# tiips_tag.net
KiCad netlist of a schematic drawn in EAGLE
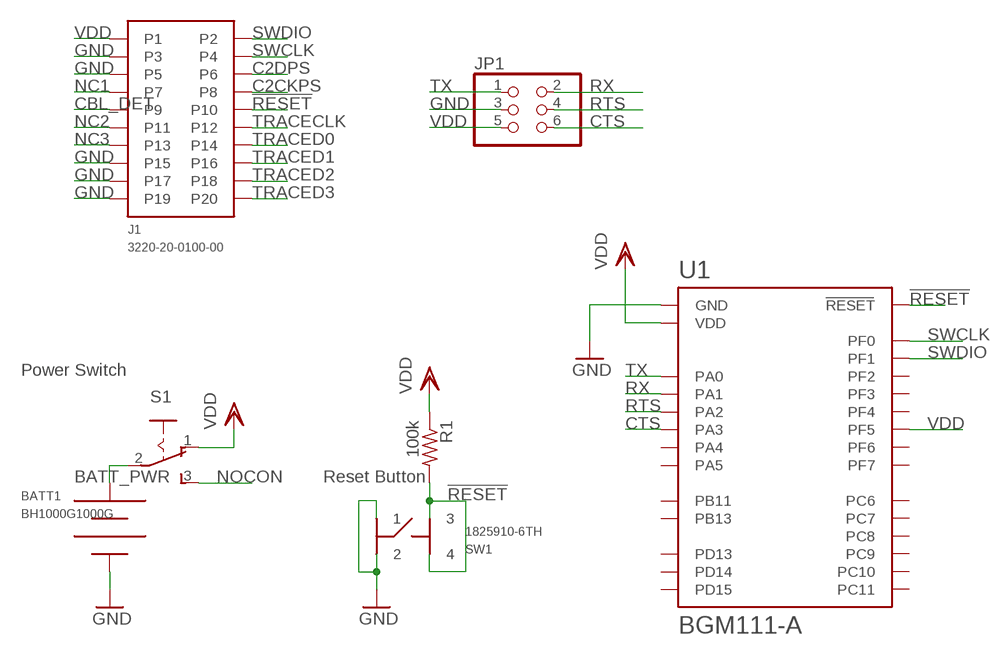
[diagram p0: schematic, sheet 1]

(export (version "E")
  (design (tool "Eeschema 10.0.6"))
  (components
    (comp (ref "BATT1")
      (value "BH1000G1000G")
      (footprint "eagle-import:BH")
      (libsource (lib "eagle-import") (part "BH1000G1000G"))
    )
    (comp (ref "J1")
      (value "3220-20-0100-00")
      (footprint "eagle-import:3220-20-0100-00")
      (libsource (lib "eagle-import") (part "3220-20-0100-00"))
    )
    (comp (ref "JP1")
      (value "PINHD-2X3")
      (footprint "eagle-import:2X03")
      (libsource (lib "eagle-import") (part "PINHD-2X3"))
    )
    (comp (ref "R1")
      (value "100k")
      (footprint "eagle-import:0309_10")
      (libsource (lib "eagle-import") (part "R-US_0309/10"))
    )
    (comp (ref "S1")
      (value "M251")
      (footprint "eagle-import:M251")
      (libsource (lib "eagle-import") (part "M251"))
    )
    (comp (ref "SW1")
      (value "1825910-6TH")
      (footprint "eagle-import:1825910-6")
      (libsource (lib "eagle-import") (part "1825910-6TH"))
    )
    (comp (ref "U1")
      (value "BGM111-A")
      (footprint "eagle-import:BGM111-A")
      (libsource (lib "eagle-import") (part "BGM111-A"))
    )
  )
  (nets
    (net (code "1") (name "/BATT_PWR") (class "Default")
      (node (ref "BATT1") (pin "2") (pinfunction "3V_2") (pintype "power_in"))
      (node (ref "S1") (pin "2") (pinfunction "P_2") (pintype "passive"))
    )
    (net (code "2") (name "/C2CKPS") (class "Default")
      (node (ref "J1") (pin "P8") (pinfunction "P8_P8") (pintype "bidirectional"))
    )
    (net (code "3") (name "/C2DPS") (class "Default")
      (node (ref "J1") (pin "P6") (pinfunction "P6_P6") (pintype "bidirectional"))
    )
    (net (code "4") (name "/CBL_DET") (class "Default")
      (node (ref "J1") (pin "P9") (pinfunction "P9_P9") (pintype "bidirectional"))
    )
    (net (code "5") (name "/CTS") (class "Default")
      (node (ref "JP1") (pin "6") (pinfunction "6_6") (pintype "passive"))
      (node (ref "U1") (pin "PA3") (pinfunction "PA3_PA3") (pintype "bidirectional"))
    )
    (net (code "6") (name "/NC1") (class "Default")
      (node (ref "J1") (pin "P7") (pinfunction "P7_P7") (pintype "bidirectional"))
    )
    (net (code "7") (name "/NC2") (class "Default")
      (node (ref "J1") (pin "P11") (pinfunction "P11_P11") (pintype "bidirectional"))
    )
    (net (code "8") (name "/NC3") (class "Default")
      (node (ref "J1") (pin "P13") (pinfunction "P13_P13") (pintype "bidirectional"))
    )
    (net (code "9") (name "/NOCON") (class "Default")
      (node (ref "S1") (pin "3") (pinfunction "S_3") (pintype "passive"))
    )
    (net (code "10") (name "/RTS") (class "Default")
      (node (ref "JP1") (pin "4") (pinfunction "4_4") (pintype "passive"))
      (node (ref "U1") (pin "PA2") (pinfunction "PA2_PA2") (pintype "bidirectional"))
    )
    (net (code "11") (name "/RX") (class "Default")
      (node (ref "JP1") (pin "2") (pinfunction "2_2") (pintype "passive"))
      (node (ref "U1") (pin "PA1") (pinfunction "PA1_PA1") (pintype "bidirectional"))
    )
    (net (code "12") (name "/SWCLK") (class "Default")
      (node (ref "J1") (pin "P4") (pinfunction "P4_P4") (pintype "bidirectional"))
      (node (ref "U1") (pin "PF0") (pinfunction "PF0_PF0") (pintype "bidirectional"))
    )
    (net (code "13") (name "/SWDIO") (class "Default")
      (node (ref "J1") (pin "P2") (pinfunction "P2_P2") (pintype "bidirectional"))
      (node (ref "U1") (pin "PF1") (pinfunction "PF1_PF1") (pintype "bidirectional"))
    )
    (net (code "14") (name "/TRACECLK") (class "Default")
      (node (ref "J1") (pin "P12") (pinfunction "P12_P12") (pintype "bidirectional"))
    )
    (net (code "15") (name "/TRACED0") (class "Default")
      (node (ref "J1") (pin "P14") (pinfunction "P14_P14") (pintype "bidirectional"))
    )
    (net (code "16") (name "/TRACED1") (class "Default")
      (node (ref "J1") (pin "P16") (pinfunction "P16_P16") (pintype "bidirectional"))
    )
    (net (code "17") (name "/TRACED2") (class "Default")
      (node (ref "J1") (pin "P18") (pinfunction "P18_P18") (pintype "bidirectional"))
    )
    (net (code "18") (name "/TRACED3") (class "Default")
      (node (ref "J1") (pin "P20") (pinfunction "P20_P20") (pintype "bidirectional"))
    )
    (net (code "19") (name "/TX") (class "Default")
      (node (ref "JP1") (pin "1") (pinfunction "1_1") (pintype "passive"))
      (node (ref "U1") (pin "PA0") (pinfunction "PA0_PA0") (pintype "bidirectional"))
    )
    (net (code "20") (name "/~{RESET}") (class "Default")
      (node (ref "J1") (pin "P10") (pinfunction "P10_P10") (pintype "bidirectional"))
      (node (ref "R1") (pin "2") (pinfunction "2_2") (pintype "passive"))
      (node (ref "SW1") (pin "3") (pinfunction "3_3") (pintype "power_in"))
      (node (ref "SW1") (pin "4") (pinfunction "4_4") (pintype "power_in"))
      (node (ref "U1") (pin "RESET") (pinfunction "RESET_RESET") (pintype "input"))
    )
    (net (code "21") (name "GND") (class "Default")
      (node (ref "BATT1") (pin "1") (pinfunction "GND_1") (pintype "power_in"))
      (node (ref "J1") (pin "P15") (pinfunction "P15_P15") (pintype "bidirectional"))
      (node (ref "J1") (pin "P17") (pinfunction "P17_P17") (pintype "bidirectional"))
      (node (ref "J1") (pin "P19") (pinfunction "P19_P19") (pintype "bidirectional"))
      (node (ref "J1") (pin "P3") (pinfunction "P3_P3") (pintype "bidirectional"))
      (node (ref "J1") (pin "P5") (pinfunction "P5_P5") (pintype "bidirectional"))
      (node (ref "JP1") (pin "3") (pinfunction "3_3") (pintype "passive"))
      (node (ref "SW1") (pin "1") (pinfunction "1_1") (pintype "power_in"))
      (node (ref "SW1") (pin "2") (pinfunction "2_2") (pintype "power_in"))
      (node (ref "U1") (pin "GND") (pinfunction "GND_GND") (pintype "power_in"))
      (node (ref "U1") (pin "GND@2") (pinfunction "GND_GND@2") (pintype "power_in"))
      (node (ref "U1") (pin "GND@3") (pinfunction "GND_GND@3") (pintype "power_in"))
      (node (ref "U1") (pin "GND@4") (pinfunction "GND_GND@4") (pintype "power_in"))
    )
    (net (code "22") (name "VDD") (class "Default")
      (node (ref "J1") (pin "P1") (pinfunction "P1_P1") (pintype "bidirectional"))
      (node (ref "JP1") (pin "5") (pinfunction "5_5") (pintype "passive"))
      (node (ref "R1") (pin "1") (pinfunction "1_1") (pintype "passive"))
      (node (ref "S1") (pin "1") (pinfunction "O_1") (pintype "passive"))
      (node (ref "U1") (pin "PF5") (pinfunction "PF5_PF5") (pintype "bidirectional"))
      (node (ref "U1") (pin "VDD") (pinfunction "VDD_VDD") (pintype "power_in"))
    )
    (net (code "23") (name "unconnected-(U1-PadPA4)") (class "Default")
      (node (ref "U1") (pin "PA4") (pinfunction "PA4_PA4") (pintype "bidirectional"))
    )
    (net (code "24") (name "unconnected-(U1-PadPA5)") (class "Default")
      (node (ref "U1") (pin "PA5") (pinfunction "PA5_PA5") (pintype "bidirectional"))
    )
    (net (code "25") (name "unconnected-(U1-PadPB11)") (class "Default")
      (node (ref "U1") (pin "PB11") (pinfunction "PB11_PB11") (pintype "bidirectional"))
    )
    (net (code "26") (name "unconnected-(U1-PadPB13)") (class "Default")
      (node (ref "U1") (pin "PB13") (pinfunction "PB13_PB13") (pintype "bidirectional"))
    )
    (net (code "27") (name "unconnected-(U1-PadPC6)") (class "Default")
      (node (ref "U1") (pin "PC6") (pinfunction "PC6_PC6") (pintype "bidirectional"))
    )
    (net (code "28") (name "unconnected-(U1-PadPC7)") (class "Default")
      (node (ref "U1") (pin "PC7") (pinfunction "PC7_PC7") (pintype "bidirectional"))
    )
    (net (code "29") (name "unconnected-(U1-PadPC8)") (class "Default")
      (node (ref "U1") (pin "PC8") (pinfunction "PC8_PC8") (pintype "bidirectional"))
    )
    (net (code "30") (name "unconnected-(U1-PadPC9)") (class "Default")
      (node (ref "U1") (pin "PC9") (pinfunction "PC9_PC9") (pintype "bidirectional"))
    )
    (net (code "31") (name "unconnected-(U1-PadPC10)") (class "Default")
      (node (ref "U1") (pin "PC10") (pinfunction "PC10_PC10") (pintype "bidirectional"))
    )
    (net (code "32") (name "unconnected-(U1-PadPC11)") (class "Default")
      (node (ref "U1") (pin "PC11") (pinfunction "PC11_PC11") (pintype "bidirectional"))
    )
    (net (code "33") (name "unconnected-(U1-PadPD13)") (class "Default")
      (node (ref "U1") (pin "PD13") (pinfunction "PD13_PD13") (pintype "bidirectional"))
    )
    (net (code "34") (name "unconnected-(U1-PadPD14)") (class "Default")
      (node (ref "U1") (pin "PD14") (pinfunction "PD14_PD14") (pintype "bidirectional"))
    )
    (net (code "35") (name "unconnected-(U1-PadPD15)") (class "Default")
      (node (ref "U1") (pin "PD15") (pinfunction "PD15_PD15") (pintype "bidirectional"))
    )
    (net (code "36") (name "unconnected-(U1-PadPF2)") (class "Default")
      (node (ref "U1") (pin "PF2") (pinfunction "PF2_PF2") (pintype "bidirectional"))
    )
    (net (code "37") (name "unconnected-(U1-PadPF3)") (class "Default")
      (node (ref "U1") (pin "PF3") (pinfunction "PF3_PF3") (pintype "bidirectional"))
    )
    (net (code "38") (name "unconnected-(U1-PadPF4)") (class "Default")
      (node (ref "U1") (pin "PF4") (pinfunction "PF4_PF4") (pintype "bidirectional"))
    )
    (net (code "39") (name "unconnected-(U1-PadPF6)") (class "Default")
      (node (ref "U1") (pin "PF6") (pinfunction "PF6_PF6") (pintype "bidirectional"))
    )
    (net (code "40") (name "unconnected-(U1-PadPF7)") (class "Default")
      (node (ref "U1") (pin "PF7") (pinfunction "PF7_PF7") (pintype "bidirectional"))
    )
  )
)
